# Sheet1.net
KiCad netlist of a schematic drawn in Altium Designer
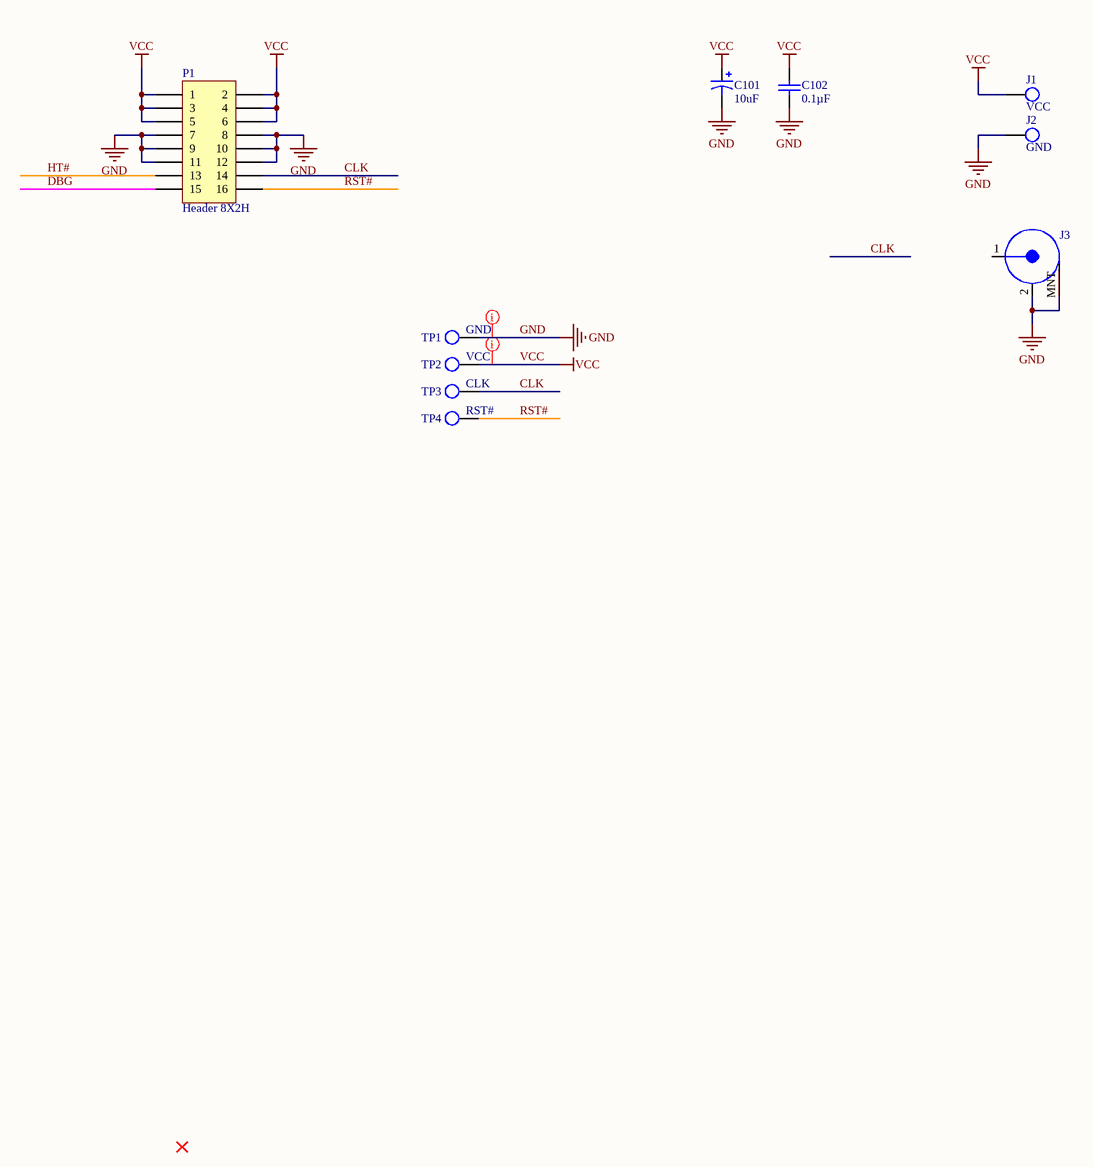
[diagram p0: Sheet1.SchDoc]

(export (version "E")
  (design (tool "Eeschema 10.0.6"))
  (components
    (comp (ref "C101")
      (value "10uF")
      (footprint "C5x7")
      (description "Polarized Capacitor")
      (fields (field (name "Comment") "Cap Pol5") (field (name "PUBLISHER") "Altium Limited"))
      (libsource (lib "Miscellaneous Devices") (part "Cap Pol5"))
    )
    (comp (ref "C102")
      (value "K104K15X7RF5TL2")
      (footprint "VISH-K104K15X7RF5TL2")
      (description "Ceramic Capacitor, 100 nF, +/- 10%, 50 V, -55 to 125 degC, 2-Pin THD, RoHS, Tape and Reel")
      (fields
        (field (name "MANUFACTURER") "Vishay")
        (field (name "TOLERANCE") "±10%")
        (field (name "CAPACITANCE") "0.1µF")
      )
      (libsource (lib "Altium Content Vault") (part "CAP-NP-2"))
    )
    (comp (ref "J1")
      (value "VCC")
      (footprint "CT3151SP-2")
      (description "CONN BANANA JACK SOLDER RED")
      (libsource (lib "TP") (part "CT3151SP-2"))
    )
    (comp (ref "J2")
      (value "GND")
      (footprint "CT3151SP-0")
      (description "CONN BANANA JACK SOLDER BLACK")
      (libsource (lib "TP") (part "CT3151SP-0"))
    )
    (comp (ref "J3") (value "RF") (footprint "BNC R/A") (libsource (lib "ModularPayload") (part "RF")))
    (comp (ref "P1")
      (value "Header 8X2H")
      (footprint "HDR2X8H")
      (description "Header, 8-Pin, Dual row, Right Angle")
      (fields (field (name "PUBLISHER") "Altium Limited"))
      (libsource (lib "Miscellaneous Connectors") (part "Header 8X2H"))
    )
    (comp (ref "TP1") (value "GND") (footprint "KSTN-5011_V") (libsource (lib "TP") (part "TP")))
    (comp (ref "TP2") (value "VCC") (footprint "KSTN-5011_V") (libsource (lib "TP") (part "TP")))
    (comp (ref "TP3") (value "CLK") (footprint "KSTN-5011_V") (libsource (lib "TP") (part "TP")))
    (comp (ref "TP4") (value "RST#") (footprint "KSTN-5011_V") (libsource (lib "TP") (part "TP")))
  )
  (nets
    (net (code "1") (name "/CLK") (class "Default")
      (node (ref "P1") (pin "14") (pinfunction "14_14") (pintype "passive"))
      (node (ref "TP3") (pin "1") (pintype "passive"))
    )
    (net (code "2") (name "/DBG") (class "Default")
      (node (ref "P1") (pin "15") (pinfunction "15_15") (pintype "passive"))
    )
    (net (code "3") (name "/HT#") (class "Default")
      (node (ref "P1") (pin "13") (pinfunction "13_13") (pintype "passive"))
    )
    (net (code "4") (name "/RST#") (class "Default")
      (node (ref "P1") (pin "16") (pinfunction "16_16") (pintype "passive"))
      (node (ref "TP4") (pin "1") (pintype "passive"))
    )
    (net (code "5") (name "GND") (class "Default")
      (node (ref "C101") (pin "2") (pinfunction "2_2") (pintype "passive"))
      (node (ref "C102") (pin "2") (pinfunction "2_2") (pintype "passive"))
      (node (ref "J2") (pin "1") (pintype "passive"))
      (node (ref "J3") (pin "2") (pintype "passive"))
      (node (ref "J3") (pin "MNT") (pinfunction "MNT_MNT") (pintype "passive"))
      (node (ref "P1") (pin "10") (pinfunction "10_10") (pintype "passive"))
      (node (ref "P1") (pin "11") (pinfunction "11_11") (pintype "passive"))
      (node (ref "P1") (pin "12") (pinfunction "12_12") (pintype "passive"))
      (node (ref "P1") (pin "7") (pinfunction "7_7") (pintype "passive"))
      (node (ref "P1") (pin "8") (pinfunction "8_8") (pintype "passive"))
      (node (ref "P1") (pin "9") (pinfunction "9_9") (pintype "passive"))
      (node (ref "TP1") (pin "1") (pintype "passive"))
    )
    (net (code "6") (name "VCC") (class "Default")
      (node (ref "C101") (pin "1") (pinfunction "1_1") (pintype "passive"))
      (node (ref "C102") (pin "1") (pinfunction "1_1") (pintype "passive"))
      (node (ref "J1") (pin "1") (pintype "passive"))
      (node (ref "P1") (pin "1") (pinfunction "1_1") (pintype "passive"))
      (node (ref "P1") (pin "2") (pinfunction "2_2") (pintype "passive"))
      (node (ref "P1") (pin "3") (pinfunction "3_3") (pintype "passive"))
      (node (ref "P1") (pin "4") (pinfunction "4_4") (pintype "passive"))
      (node (ref "P1") (pin "5") (pinfunction "5_5") (pintype "passive"))
      (node (ref "P1") (pin "6") (pinfunction "6_6") (pintype "passive"))
      (node (ref "TP2") (pin "1") (pintype "passive"))
    )
    (net (code "7") (name "unconnected-(J3-Pad1)") (class "Default")
      (node (ref "J3") (pin "1") (pintype "passive"))
    )
  )
)
